# CAR.net
KiCad netlist of a schematic drawn in Altium Designer
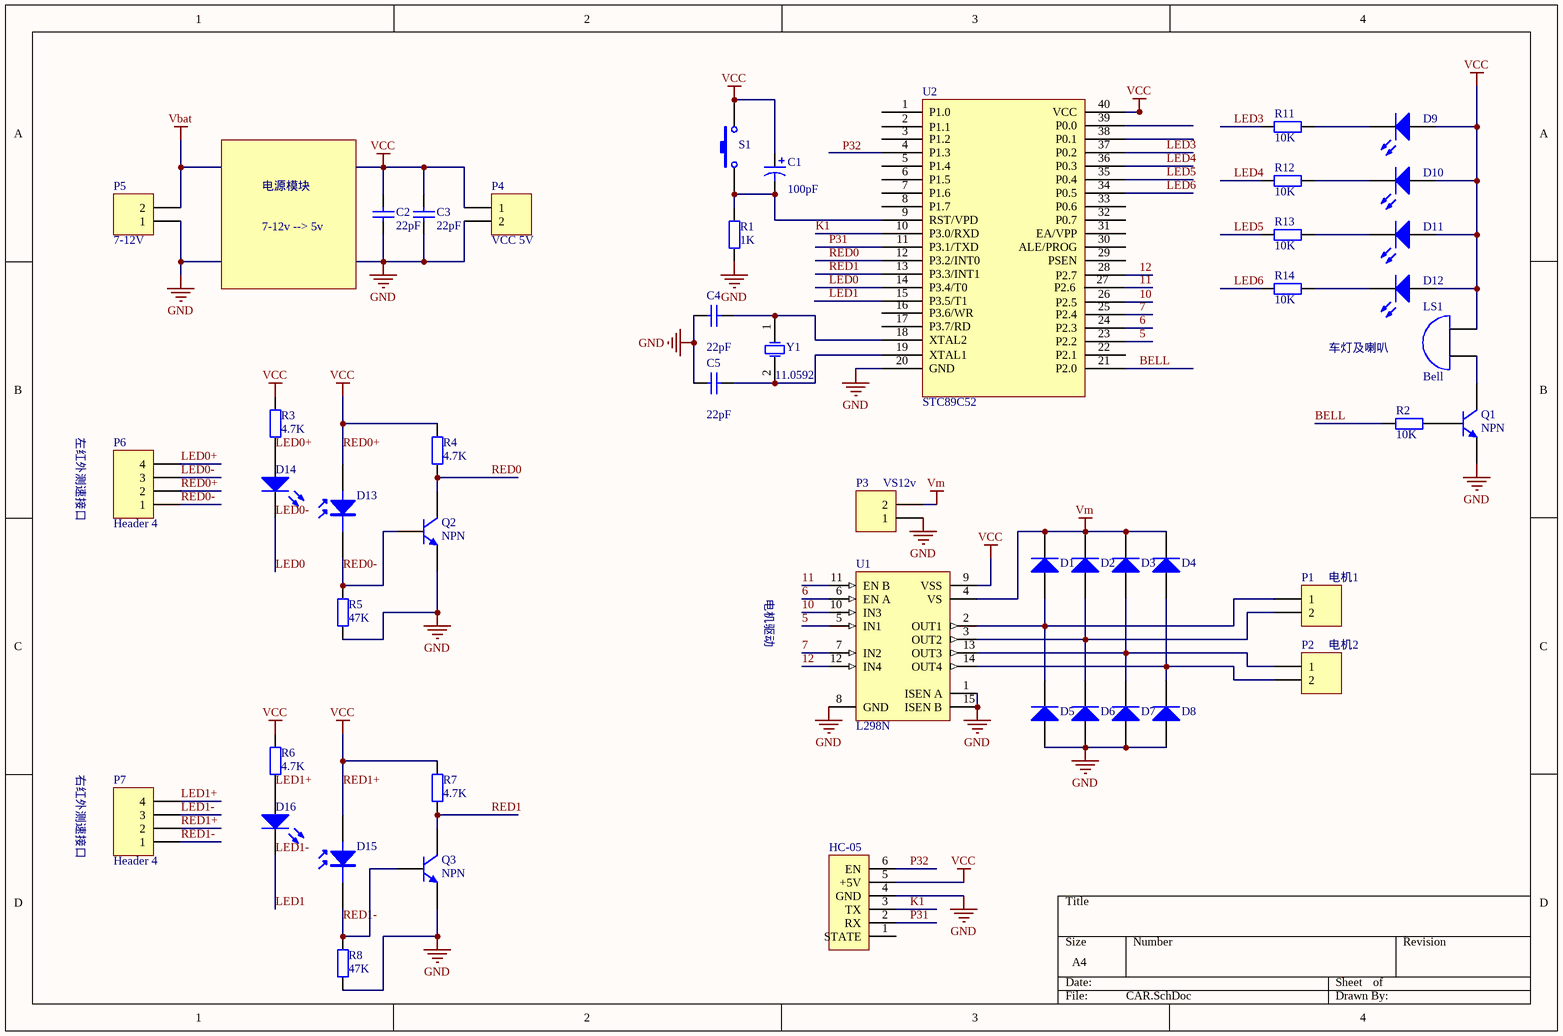
[diagram p0: CAR.SchDoc]

(export (version "E")
  (design (tool "Eeschema 10.0.6"))
  (components
    (comp (ref "C1")
      (value "100pF")
      (footprint "CAPPR1.5-4x5")
      (description "Polarized Capacitor (Radial)")
      (fields (field (name "Comment") "Cap Pol1") (field (name "PUBLISHER") "Altium Limited"))
      (libsource (lib "Miscellaneous Devices") (part "Cap Pol1"))
    )
    (comp (ref "C2")
      (value "22pF")
      (footprint "CAPR2.54-5.1x3.2")
      (description "Capacitor")
      (fields (field (name "Comment") "Cap") (field (name "PUBLISHER") "Altium Limited"))
      (libsource (lib "Miscellaneous Devices") (part "Cap"))
    )
    (comp (ref "C3")
      (value "22pF")
      (footprint "CAPR2.54-5.1x3.2")
      (description "Capacitor")
      (fields (field (name "Comment") "Cap") (field (name "PUBLISHER") "Altium Limited"))
      (libsource (lib "Miscellaneous Devices") (part "Cap"))
    )
    (comp (ref "C4")
      (value "22pF")
      (footprint "CAPR2.54-5.1x3.2")
      (description "Capacitor")
      (fields (field (name "Comment") "Cap") (field (name "PUBLISHER") "Altium Limited"))
      (libsource (lib "Miscellaneous Devices") (part "Cap"))
    )
    (comp (ref "C5")
      (value "22pF")
      (footprint "CAPR2.54-5.1x3.2")
      (description "Capacitor")
      (fields (field (name "Comment") "Cap") (field (name "PUBLISHER") "Altium Limited"))
      (libsource (lib "Miscellaneous Devices") (part "Cap"))
    )
    (comp (ref "D1")
      (value "Diode 1N914")
      (footprint "DIO7.1-3.9x1.9")
      (description "High Conductance Fast Diode")
      (fields (field (name "PUBLISHER") "Altium Limited"))
      (libsource (lib "Miscellaneous Devices") (part "Diode 1N914"))
    )
    (comp (ref "D2")
      (value "Diode 1N914")
      (footprint "DIO7.1-3.9x1.9")
      (description "High Conductance Fast Diode")
      (fields (field (name "PUBLISHER") "Altium Limited"))
      (libsource (lib "Miscellaneous Devices") (part "Diode 1N914"))
    )
    (comp (ref "D3")
      (value "Diode 1N914")
      (footprint "DIO7.1-3.9x1.9")
      (description "High Conductance Fast Diode")
      (fields (field (name "PUBLISHER") "Altium Limited"))
      (libsource (lib "Miscellaneous Devices") (part "Diode 1N914"))
    )
    (comp (ref "D4")
      (value "Diode 1N914")
      (footprint "DIO7.1-3.9x1.9")
      (description "High Conductance Fast Diode")
      (fields (field (name "PUBLISHER") "Altium Limited"))
      (libsource (lib "Miscellaneous Devices") (part "Diode 1N914"))
    )
    (comp (ref "D5")
      (value "Diode 1N914")
      (footprint "DIO7.1-3.9x1.9")
      (description "High Conductance Fast Diode")
      (fields (field (name "PUBLISHER") "Altium Limited"))
      (libsource (lib "Miscellaneous Devices") (part "Diode 1N914"))
    )
    (comp (ref "D6")
      (value "Diode 1N914")
      (footprint "DIO7.1-3.9x1.9")
      (description "High Conductance Fast Diode")
      (fields (field (name "PUBLISHER") "Altium Limited"))
      (libsource (lib "Miscellaneous Devices") (part "Diode 1N914"))
    )
    (comp (ref "D7")
      (value "Diode 1N914")
      (footprint "DIO7.1-3.9x1.9")
      (description "High Conductance Fast Diode")
      (fields (field (name "PUBLISHER") "Altium Limited"))
      (libsource (lib "Miscellaneous Devices") (part "Diode 1N914"))
    )
    (comp (ref "D8")
      (value "Diode 1N914")
      (footprint "DIO7.1-3.9x1.9")
      (description "High Conductance Fast Diode")
      (fields (field (name "PUBLISHER") "Altium Limited"))
      (libsource (lib "Miscellaneous Devices") (part "Diode 1N914"))
    )
    (comp (ref "D9")
      (value "~")
      (footprint "DIO7.1-3.9x1.9")
      (description "Typical INFRARED GaAs LED")
      (fields (field (name "PUBLISHER") "Altium Limited"))
      (libsource (lib "Miscellaneous Devices") (part "LED0"))
    )
    (comp (ref "D10")
      (value "~")
      (footprint "DIO7.1-3.9x1.9")
      (description "Typical INFRARED GaAs LED")
      (fields (field (name "PUBLISHER") "Altium Limited"))
      (libsource (lib "Miscellaneous Devices") (part "LED0"))
    )
    (comp (ref "D11")
      (value "~")
      (footprint "DIO7.1-3.9x1.9")
      (description "Typical INFRARED GaAs LED")
      (fields (field (name "PUBLISHER") "Altium Limited"))
      (libsource (lib "Miscellaneous Devices") (part "LED0"))
    )
    (comp (ref "D12")
      (value "~")
      (footprint "DIO7.1-3.9x1.9")
      (description "Typical INFRARED GaAs LED")
      (fields (field (name "PUBLISHER") "Altium Limited"))
      (libsource (lib "Miscellaneous Devices") (part "LED0"))
    )
    (comp (ref "D13") (value "RED") (footprint "LED-1") (libsource (lib "MyLib") (part "LED_RCV")))
    (comp (ref "D14")
      (value "~")
      (footprint "LED-1")
      (description "Typical INFRARED GaAs LED")
      (fields (field (name "PUBLISHER") "Altium Limited"))
      (libsource (lib "Miscellaneous Devices") (part "LED0"))
    )
    (comp (ref "D15") (value "RED") (footprint "LED-1") (libsource (lib "MyLib") (part "LED_RCV")))
    (comp (ref "D16")
      (value "~")
      (footprint "LED-1")
      (description "Typical INFRARED GaAs LED")
      (fields (field (name "PUBLISHER") "Altium Limited"))
      (libsource (lib "Miscellaneous Devices") (part "LED0"))
    )
    (comp (ref "HC-05")
      (value "Header 6")
      (footprint "HDR1X6")
      (description "Header, 6-Pin")
      (fields (field (name "PUBLISHER") "Altium Limited"))
      (libsource (lib "Miscellaneous Connectors") (part "Header 6"))
    )
    (comp (ref "LS1")
      (value "Bell")
      (footprint "PIN2")
      (description "Electrical Bell")
      (fields (field (name "PUBLISHER") "Altium Limited"))
      (libsource (lib "Miscellaneous Devices") (part "Bell"))
    )
    (comp (ref "P1")
      (value "电机1")
      (footprint "HDR1X2")
      (description "Header, 2-Pin")
      (fields (field (name "PUBLISHER") "Altium Limited"))
      (libsource (lib "") (part "Header 2_1"))
    )
    (comp (ref "P2")
      (value "电机2")
      (footprint "HDR1X2")
      (description "Header, 2-Pin")
      (fields (field (name "PUBLISHER") "Altium Limited"))
      (libsource (lib "") (part "Header 2_1"))
    )
    (comp (ref "P3")
      (value "VS12v")
      (footprint "HDR1X2")
      (description "Header, 2-Pin")
      (fields (field (name "PUBLISHER") "Altium Limited"))
      (libsource (lib "Miscellaneous Connectors") (part "Header 2"))
    )
    (comp (ref "P4")
      (value "VCC 5V")
      (footprint "HDR1X2")
      (description "Header, 2-Pin")
      (fields (field (name "PUBLISHER") "Altium Limited"))
      (libsource (lib "") (part "Header 2_1"))
    )
    (comp (ref "P5")
      (value "7-12V")
      (footprint "HDR1X2")
      (description "Header, 2-Pin")
      (fields (field (name "PUBLISHER") "Altium Limited"))
      (libsource (lib "Miscellaneous Connectors") (part "Header 2"))
    )
    (comp (ref "P6")
      (value "Header 4")
      (footprint "HDR1X4")
      (description "Header, 4-Pin")
      (fields (field (name "PUBLISHER") "Altium Limited"))
      (libsource (lib "Miscellaneous Connectors") (part "Header 4"))
    )
    (comp (ref "P7")
      (value "Header 4")
      (footprint "HDR1X4")
      (description "Header, 4-Pin")
      (fields (field (name "PUBLISHER") "Altium Limited"))
      (libsource (lib "Miscellaneous Connectors") (part "Header 4"))
    )
    (comp (ref "Q1")
      (value "NPN")
      (footprint "BCY-W3")
      (description "NPN Bipolar Transistor")
      (fields (field (name "PUBLISHER") "Altium Limited"))
      (libsource (lib "Miscellaneous Devices") (part "NPN"))
    )
    (comp (ref "Q2")
      (value "NPN")
      (footprint "BCY-W3")
      (description "NPN Bipolar Transistor")
      (fields (field (name "PUBLISHER") "Altium Limited"))
      (libsource (lib "Miscellaneous Devices") (part "NPN"))
    )
    (comp (ref "Q3")
      (value "NPN")
      (footprint "BCY-W3")
      (description "NPN Bipolar Transistor")
      (fields (field (name "PUBLISHER") "Altium Limited"))
      (libsource (lib "Miscellaneous Devices") (part "NPN"))
    )
    (comp (ref "R1")
      (value "1K")
      (footprint "AXIAL-0.4")
      (description "Resistor")
      (fields (field (name "Comment") "Res2") (field (name "PUBLISHER") "Altium Limited"))
      (libsource (lib "") (part "Res2_2"))
    )
    (comp (ref "R2")
      (value "10K")
      (footprint "AXIAL-0.4")
      (description "Resistor")
      (fields (field (name "PUBLISHER") "Altium Limited"))
      (libsource (lib "") (part "Res2_1"))
    )
    (comp (ref "R3")
      (value "4.7K")
      (footprint "AXIAL-0.4")
      (description "Resistor")
      (fields (field (name "PUBLISHER") "Altium Limited"))
      (libsource (lib "Miscellaneous Devices") (part "Res2"))
    )
    (comp (ref "R4")
      (value "4.7K")
      (footprint "AXIAL-0.4")
      (description "Resistor")
      (fields (field (name "PUBLISHER") "Altium Limited"))
      (libsource (lib "Miscellaneous Devices") (part "Res2"))
    )
    (comp (ref "R5")
      (value "47K")
      (footprint "AXIAL-0.4")
      (description "Resistor")
      (fields (field (name "PUBLISHER") "Altium Limited"))
      (libsource (lib "Miscellaneous Devices") (part "Res2"))
    )
    (comp (ref "R6")
      (value "4.7K")
      (footprint "AXIAL-0.4")
      (description "Resistor")
      (fields (field (name "PUBLISHER") "Altium Limited"))
      (libsource (lib "Miscellaneous Devices") (part "Res2"))
    )
    (comp (ref "R7")
      (value "4.7K")
      (footprint "AXIAL-0.4")
      (description "Resistor")
      (fields (field (name "PUBLISHER") "Altium Limited"))
      (libsource (lib "Miscellaneous Devices") (part "Res2"))
    )
    (comp (ref "R8")
      (value "47K")
      (footprint "AXIAL-0.4")
      (description "Resistor")
      (fields (field (name "PUBLISHER") "Altium Limited"))
      (libsource (lib "Miscellaneous Devices") (part "Res2"))
    )
    (comp (ref "R11")
      (value "10K")
      (footprint "AXIAL-0.4")
      (description "Resistor")
      (fields (field (name "PUBLISHER") "Altium Limited"))
      (libsource (lib "") (part "Res2_1"))
    )
    (comp (ref "R12")
      (value "10K")
      (footprint "AXIAL-0.4")
      (description "Resistor")
      (fields (field (name "PUBLISHER") "Altium Limited"))
      (libsource (lib "") (part "Res2_1"))
    )
    (comp (ref "R13")
      (value "10K")
      (footprint "AXIAL-0.4")
      (description "Resistor")
      (fields (field (name "PUBLISHER") "Altium Limited"))
      (libsource (lib "") (part "Res2_1"))
    )
    (comp (ref "R14")
      (value "10K")
      (footprint "AXIAL-0.4")
      (description "Resistor")
      (fields (field (name "PUBLISHER") "Altium Limited"))
      (libsource (lib "") (part "Res2_1"))
    )
    (comp (ref "S1")
      (value "SW-PB")
      (footprint "SPST-2")
      (description "Switch")
      (fields (field (name "PUBLISHER") "Altium Limited"))
      (libsource (lib "Miscellaneous Devices") (part "SW-PB"))
    )
    (comp (ref "U1")
      (value "L298N")
      (footprint "Multiwatt15V")
      (description "Dual Full Bridge Driver")
      (fields (field (name "PUBLISHER") "Altium Limited"))
      (libsource (lib "ST Interface DC Motor Controller") (part "L298N"))
    )
    (comp (ref "U2") (value "STC89C52") (footprint "DIP-40") (libsource (lib "STC89C52") (part "STC89C52")))
    (comp (ref "Y1")
      (value "XTAL")
      (footprint "BCY-W2/D3.1")
      (description "Crystal Oscillator")
      (fields (field (name "PUBLISHER") "11.0592"))
      (libsource (lib "Miscellaneous Devices") (part "XTAL"))
    )
  )
  (nets
    (net (code "1") (name "/5") (class "Default")
      (node (ref "U1") (pin "5") (pinfunction "IN1_5") (pintype "input"))
      (node (ref "U2") (pin "23") (pinfunction "P2.2_23") (pintype "passive"))
    )
    (net (code "2") (name "/6") (class "Default")
      (node (ref "U1") (pin "6") (pinfunction "EN_A_6") (pintype "input"))
      (node (ref "U2") (pin "24") (pinfunction "P2.3_24") (pintype "passive"))
    )
    (net (code "3") (name "/7") (class "Default")
      (node (ref "U1") (pin "7") (pinfunction "IN2_7") (pintype "input"))
      (node (ref "U2") (pin "25") (pinfunction "P2.4_25") (pintype "passive"))
    )
    (net (code "4") (name "/10") (class "Default")
      (node (ref "U1") (pin "10") (pinfunction "IN3_10") (pintype "input"))
      (node (ref "U2") (pin "26") (pinfunction "P2.5_26") (pintype "passive"))
    )
    (net (code "5") (name "/11") (class "Default")
      (node (ref "U1") (pin "11") (pinfunction "EN_B_11") (pintype "input"))
      (node (ref "U2") (pin "27") (pinfunction "P2.6_27") (pintype "passive"))
    )
    (net (code "6") (name "/12") (class "Default")
      (node (ref "U1") (pin "12") (pinfunction "IN4_12") (pintype "input"))
      (node (ref "U2") (pin "28") (pinfunction "P2.7_28") (pintype "passive"))
    )
    (net (code "7") (name "/BELL") (class "Default")
      (node (ref "R2") (pin "2") (pinfunction "2_2") (pintype "passive"))
      (node (ref "U2") (pin "21") (pinfunction "P2.0_21") (pintype "passive"))
    )
    (net (code "8") (name "/K1") (class "Default")
      (node (ref "HC-05") (pin "3") (pinfunction "TX_3") (pintype "passive"))
      (node (ref "U2") (pin "10") (pinfunction "P3.0/RXD_10") (pintype "passive"))
    )
    (net (code "9") (name "/LED0") (class "Default")
      (node (ref "D14") (pin "2") (pinfunction "K_2") (pintype "passive"))
      (node (ref "P6") (pin "3") (pinfunction "3_3") (pintype "passive"))
      (node (ref "U2") (pin "14") (pinfunction "P3.4/T0_14") (pintype "passive"))
    )
    (net (code "10") (name "/LED0+") (class "Default")
      (node (ref "D14") (pin "1") (pinfunction "A_1") (pintype "passive"))
      (node (ref "P6") (pin "4") (pinfunction "4_4") (pintype "passive"))
      (node (ref "R3") (pin "1") (pinfunction "1_1") (pintype "passive"))
    )
    (net (code "11") (name "/LED1") (class "Default")
      (node (ref "D16") (pin "2") (pinfunction "K_2") (pintype "passive"))
      (node (ref "P7") (pin "3") (pinfunction "3_3") (pintype "passive"))
      (node (ref "U2") (pin "15") (pinfunction "P3.5/T1_15") (pintype "passive"))
    )
    (net (code "12") (name "/LED1+") (class "Default")
      (node (ref "D16") (pin "1") (pinfunction "A_1") (pintype "passive"))
      (node (ref "P7") (pin "4") (pinfunction "4_4") (pintype "passive"))
      (node (ref "R6") (pin "1") (pinfunction "1_1") (pintype "passive"))
    )
    (net (code "13") (name "/LED3") (class "Default")
      (node (ref "R11") (pin "2") (pinfunction "2_2") (pintype "passive"))
      (node (ref "U2") (pin "37") (pinfunction "P0.2_37") (pintype "passive"))
    )
    (net (code "14") (name "/LED4") (class "Default")
      (node (ref "R12") (pin "2") (pinfunction "2_2") (pintype "passive"))
      (node (ref "U2") (pin "36") (pinfunction "P0.3_36") (pintype "passive"))
    )
    (net (code "15") (name "/LED5") (class "Default")
      (node (ref "R13") (pin "2") (pinfunction "2_2") (pintype "passive"))
      (node (ref "U2") (pin "35") (pinfunction "P0.4_35") (pintype "passive"))
    )
    (net (code "16") (name "/LED6") (class "Default")
      (node (ref "R14") (pin "2") (pinfunction "2_2") (pintype "passive"))
      (node (ref "U2") (pin "34") (pinfunction "P0.5_34") (pintype "passive"))
    )
    (net (code "17") (name "/P31") (class "Default")
      (node (ref "HC-05") (pin "2") (pinfunction "RX_2") (pintype "passive"))
      (node (ref "U2") (pin "11") (pinfunction "P3.1/TXD_11") (pintype "passive"))
    )
    (net (code "18") (name "/P32") (class "Default")
      (node (ref "HC-05") (pin "6") (pinfunction "EN_6") (pintype "passive"))
    )
    (net (code "19") (name "/RED0") (class "Default")
      (node (ref "Q2") (pin "1") (pinfunction "C_1") (pintype "passive"))
      (node (ref "R4") (pin "1") (pinfunction "1_1") (pintype "passive"))
      (node (ref "U2") (pin "12") (pinfunction "P3.2/INT0_12") (pintype "passive"))
    )
    (net (code "20") (name "/RED0-") (class "Default")
      (node (ref "D13") (pin "K") (pinfunction "2_K") (pintype "passive"))
      (node (ref "P6") (pin "1") (pinfunction "1_1") (pintype "passive"))
      (node (ref "Q2") (pin "2") (pinfunction "B_2") (pintype "passive"))
      (node (ref "R5") (pin "2") (pinfunction "2_2") (pintype "passive"))
    )
    (net (code "21") (name "/RED1") (class "Default")
      (node (ref "Q3") (pin "1") (pinfunction "C_1") (pintype "passive"))
      (node (ref "R7") (pin "1") (pinfunction "1_1") (pintype "passive"))
      (node (ref "U2") (pin "13") (pinfunction "P3.3/INT1_13") (pintype "passive"))
    )
    (net (code "22") (name "/RED1-") (class "Default")
      (node (ref "D15") (pin "K") (pinfunction "2_K") (pintype "passive"))
      (node (ref "P7") (pin "1") (pinfunction "1_1") (pintype "passive"))
      (node (ref "Q3") (pin "2") (pinfunction "B_2") (pintype "passive"))
      (node (ref "R8") (pin "2") (pinfunction "2_2") (pintype "passive"))
    )
    (net (code "23") (name "GND") (class "Default")
      (node (ref "C2") (pin "1") (pinfunction "1_1") (pintype "passive"))
      (node (ref "C3") (pin "1") (pinfunction "1_1") (pintype "passive"))
      (node (ref "C4") (pin "1") (pinfunction "1_1") (pintype "passive"))
      (node (ref "C5") (pin "1") (pinfunction "1_1") (pintype "passive"))
      (node (ref "D5") (pin "1") (pinfunction "A_1") (pintype "passive"))
      (node (ref "D6") (pin "1") (pinfunction "A_1") (pintype "passive"))
      (node (ref "D7") (pin "1") (pinfunction "A_1") (pintype "passive"))
      (node (ref "D8") (pin "1") (pinfunction "A_1") (pintype "passive"))
      (node (ref "HC-05") (pin "4") (pinfunction "GND_4") (pintype "passive"))
      (node (ref "P3") (pin "1") (pinfunction "1_1") (pintype "passive"))
      (node (ref "P4") (pin "2") (pinfunction "2_2") (pintype "passive"))
      (node (ref "P5") (pin "1") (pinfunction "1_1") (pintype "passive"))
      (node (ref "Q1") (pin "3") (pinfunction "E_3") (pintype "passive"))
      (node (ref "Q2") (pin "3") (pinfunction "E_3") (pintype "passive"))
      (node (ref "Q3") (pin "3") (pinfunction "E_3") (pintype "passive"))
      (node (ref "R1") (pin "1") (pinfunction "1_1") (pintype "passive"))
      (node (ref "R5") (pin "1") (pinfunction "1_1") (pintype "passive"))
      (node (ref "R8") (pin "1") (pinfunction "1_1") (pintype "passive"))
      (node (ref "U1") (pin "1") (pinfunction "ISEN_A_1") (pintype "passive"))
      (node (ref "U1") (pin "15") (pinfunction "ISEN_B_15") (pintype "passive"))
      (node (ref "U1") (pin "8") (pinfunction "GND_8") (pintype "power_in"))
      (node (ref "U2") (pin "20") (pinfunction "GND_20") (pintype "passive"))
    )
    (net (code "24") (name "Net-(D1-A)") (class "Default")
      (node (ref "D1") (pin "1") (pinfunction "A_1") (pintype "passive"))
      (node (ref "D5") (pin "2") (pinfunction "K_2") (pintype "passive"))
      (node (ref "P1") (pin "1") (pinfunction "1_1") (pintype "passive"))
      (node (ref "U1") (pin "2") (pinfunction "OUT1_2") (pintype "output"))
    )
    (net (code "25") (name "Net-(D2-A)") (class "Default")
      (node (ref "D2") (pin "1") (pinfunction "A_1") (pintype "passive"))
      (node (ref "D6") (pin "2") (pinfunction "K_2") (pintype "passive"))
      (node (ref "P1") (pin "2") (pinfunction "2_2") (pintype "passive"))
      (node (ref "U1") (pin "3") (pinfunction "OUT2_3") (pintype "output"))
    )
    (net (code "26") (name "Net-(D3-A)") (class "Default")
      (node (ref "D3") (pin "1") (pinfunction "A_1") (pintype "passive"))
      (node (ref "D7") (pin "2") (pinfunction "K_2") (pintype "passive"))
      (node (ref "P2") (pin "1") (pinfunction "1_1") (pintype "passive"))
      (node (ref "U1") (pin "13") (pinfunction "OUT3_13") (pintype "output"))
    )
    (net (code "27") (name "Net-(D4-A)") (class "Default")
      (node (ref "D4") (pin "1") (pinfunction "A_1") (pintype "passive"))
      (node (ref "D8") (pin "2") (pinfunction "K_2") (pintype "passive"))
      (node (ref "P2") (pin "2") (pinfunction "2_2") (pintype "passive"))
      (node (ref "U1") (pin "14") (pinfunction "OUT4_14") (pintype "output"))
    )
    (net (code "28") (name "Net-(D9-K)") (class "Default")
      (node (ref "D9") (pin "2") (pinfunction "K_2") (pintype "passive"))
      (node (ref "R11") (pin "1") (pinfunction "1_1") (pintype "passive"))
    )
    (net (code "29") (name "Net-(D10-K)") (class "Default")
      (node (ref "D10") (pin "2") (pinfunction "K_2") (pintype "passive"))
      (node (ref "R12") (pin "1") (pinfunction "1_1") (pintype "passive"))
    )
    (net (code "30") (name "Net-(D11-K)") (class "Default")
      (node (ref "D11") (pin "2") (pinfunction "K_2") (pintype "passive"))
      (node (ref "R13") (pin "1") (pinfunction "1_1") (pintype "passive"))
    )
    (net (code "31") (name "Net-(D12-K)") (class "Default")
      (node (ref "D12") (pin "2") (pinfunction "K_2") (pintype "passive"))
      (node (ref "R14") (pin "1") (pinfunction "1_1") (pintype "passive"))
    )
    (net (code "32") (name "Net-(LS1-A)") (class "Default")
      (node (ref "LS1") (pin "1") (pinfunction "A_1") (pintype "passive"))
      (node (ref "Q1") (pin "1") (pinfunction "C_1") (pintype "passive"))
    )
    (net (code "33") (name "Net-(Q1-B)") (class "Default")
      (node (ref "Q1") (pin "2") (pinfunction "B_2") (pintype "passive"))
      (node (ref "R2") (pin "1") (pinfunction "1_1") (pintype "passive"))
    )
    (net (code "34") (name "Net-(U2-RST{slash}VPD)") (class "Default")
      (node (ref "C1") (pin "2") (pinfunction "2_2") (pintype "passive"))
      (node (ref "R1") (pin "2") (pinfunction "2_2") (pintype "passive"))
      (node (ref "S1") (pin "1") (pinfunction "1_1") (pintype "passive"))
      (node (ref "U2") (pin "9") (pinfunction "RST/VPD_9") (pintype "passive"))
    )
    (net (code "35") (name "Net-(U2-XTAL1)") (class "Default")
      (node (ref "C5") (pin "2") (pinfunction "2_2") (pintype "passive"))
      (node (ref "U2") (pin "19") (pinfunction "XTAL1_19") (pintype "passive"))
      (node (ref "Y1") (pin "2") (pinfunction "OSC2_2") (pintype "passive"))
    )
    (net (code "36") (name "Net-(U2-XTAL2)") (class "Default")
      (node (ref "C4") (pin "2") (pinfunction "2_2") (pintype "passive"))
      (node (ref "U2") (pin "18") (pinfunction "XTAL2_18") (pintype "passive"))
      (node (ref "Y1") (pin "1") (pinfunction "OSC1_1") (pintype "passive"))
    )
    (net (code "37") (name "VCC") (class "Default")
      (node (ref "C1") (pin "1") (pinfunction "1_1") (pintype "passive"))
      (node (ref "C2") (pin "2") (pinfunction "2_2") (pintype "passive"))
      (node (ref "C3") (pin "2") (pinfunction "2_2") (pintype "passive"))
      (node (ref "D10") (pin "1") (pinfunction "A_1") (pintype "passive"))
      (node (ref "D11") (pin "1") (pinfunction "A_1") (pintype "passive"))
      (node (ref "D12") (pin "1") (pinfunction "A_1") (pintype "passive"))
      (node (ref "D13") (pin "A") (pinfunction "1_A") (pintype "passive"))
      (node (ref "D15") (pin "A") (pinfunction "1_A") (pintype "passive"))
      (node (ref "D9") (pin "1") (pinfunction "A_1") (pintype "passive"))
      (node (ref "HC-05") (pin "5") (pinfunction "+5V_5") (pintype "passive"))
      (node (ref "LS1") (pin "2") (pinfunction "B_2") (pintype "passive"))
      (node (ref "P4") (pin "1") (pinfunction "1_1") (pintype "passive"))
      (node (ref "P6") (pin "2") (pinfunction "2_2") (pintype "passive"))
      (node (ref "P7") (pin "2") (pinfunction "2_2") (pintype "passive"))
      (node (ref "R3") (pin "2") (pinfunction "2_2") (pintype "passive"))
      (node (ref "R4") (pin "2") (pinfunction "2_2") (pintype "passive"))
      (node (ref "R6") (pin "2") (pinfunction "2_2") (pintype "passive"))
      (node (ref "R7") (pin "2") (pinfunction "2_2") (pintype "passive"))
      (node (ref "S1") (pin "2") (pinfunction "2_2") (pintype "passive"))
      (node (ref "U1") (pin "9") (pinfunction "VSS_9") (pintype "power_in"))
      (node (ref "U2") (pin "40") (pinfunction "VCC_40") (pintype "passive"))
    )
    (net (code "38") (name "Vbat") (class "Default")
      (node (ref "P5") (pin "2") (pinfunction "2_2") (pintype "passive"))
    )
    (net (code "39") (name "Vm") (class "Default")
      (node (ref "D1") (pin "2") (pinfunction "K_2") (pintype "passive"))
      (node (ref "D2") (pin "2") (pinfunction "K_2") (pintype "passive"))
      (node (ref "D3") (pin "2") (pinfunction "K_2") (pintype "passive"))
      (node (ref "D4") (pin "2") (pinfunction "K_2") (pintype "passive"))
      (node (ref "P3") (pin "2") (pinfunction "2_2") (pintype "passive"))
      (node (ref "U1") (pin "4") (pinfunction "VS_4") (pintype "power_in"))
    )
    (net (code "40") (name "unconnected-(HC-05-STATE-Pad1)") (class "Default")
      (node (ref "HC-05") (pin "1") (pinfunction "STATE_1") (pintype "passive"))
    )
    (net (code "41") (name "unconnected-(U2-ALE{slash}PROG-Pad30)") (class "Default")
      (node (ref "U2") (pin "30") (pinfunction "ALE/PROG_30") (pintype "passive"))
    )
    (net (code "42") (name "unconnected-(U2-EA{slash}VPP-Pad31)") (class "Default")
      (node (ref "U2") (pin "31") (pinfunction "EA/VPP_31") (pintype "passive"))
    )
    (net (code "43") (name "unconnected-(U2-P0.0-Pad39)") (class "Default")
      (node (ref "U2") (pin "39") (pinfunction "P0.0_39") (pintype "passive"))
    )
    (net (code "44") (name "unconnected-(U2-P0.1-Pad38)") (class "Default")
      (node (ref "U2") (pin "38") (pinfunction "P0.1_38") (pintype "passive"))
    )
    (net (code "45") (name "unconnected-(U2-P0.6-Pad33)") (class "Default")
      (node (ref "U2") (pin "33") (pinfunction "P0.6_33") (pintype "passive"))
    )
    (net (code "46") (name "unconnected-(U2-P0.7-Pad32)") (class "Default")
      (node (ref "U2") (pin "32") (pinfunction "P0.7_32") (pintype "passive"))
    )
    (net (code "47") (name "unconnected-(U2-P1.0-Pad1)") (class "Default")
      (node (ref "U2") (pin "1") (pinfunction "P1.0_1") (pintype "passive"))
    )
    (net (code "48") (name "unconnected-(U2-P1.1-Pad2)") (class "Default")
      (node (ref "U2") (pin "2") (pinfunction "P1.1_2") (pintype "passive"))
    )
    (net (code "49") (name "unconnected-(U2-P1.2-Pad3)") (class "Default")
      (node (ref "U2") (pin "3") (pinfunction "P1.2_3") (pintype "passive"))
    )
    (net (code "50") (name "unconnected-(U2-P1.3-Pad4)") (class "Default")
      (node (ref "U2") (pin "4") (pinfunction "P1.3_4") (pintype "passive"))
    )
    (net (code "51") (name "unconnected-(U2-P1.4-Pad5)") (class "Default")
      (node (ref "U2") (pin "5") (pinfunction "P1.4_5") (pintype "passive"))
    )
    (net (code "52") (name "unconnected-(U2-P1.5-Pad6)") (class "Default")
      (node (ref "U2") (pin "6") (pinfunction "P1.5_6") (pintype "passive"))
    )
    (net (code "53") (name "unconnected-(U2-P1.6-Pad7)") (class "Default")
      (node (ref "U2") (pin "7") (pinfunction "P1.6_7") (pintype "passive"))
    )
    (net (code "54") (name "unconnected-(U2-P1.7-Pad8)") (class "Default")
      (node (ref "U2") (pin "8") (pinfunction "P1.7_8") (pintype "passive"))
    )
    (net (code "55") (name "unconnected-(U2-P2.1-Pad22)") (class "Default")
      (node (ref "U2") (pin "22") (pinfunction "P2.1_22") (pintype "passive"))
    )
    (net (code "56") (name "unconnected-(U2-P3.6{slash}WR-Pad16)") (class "Default")
      (node (ref "U2") (pin "16") (pinfunction "P3.6/WR_16") (pintype "passive"))
    )
    (net (code "57") (name "unconnected-(U2-P3.7{slash}RD-Pad17)") (class "Default")
      (node (ref "U2") (pin "17") (pinfunction "P3.7/RD_17") (pintype "passive"))
    )
    (net (code "58") (name "unconnected-(U2-PSEN-Pad29)") (class "Default")
      (node (ref "U2") (pin "29") (pinfunction "PSEN_29") (pintype "passive"))
    )
  )
)
